# Power.net
KiCad netlist of a schematic drawn in Altium Designer
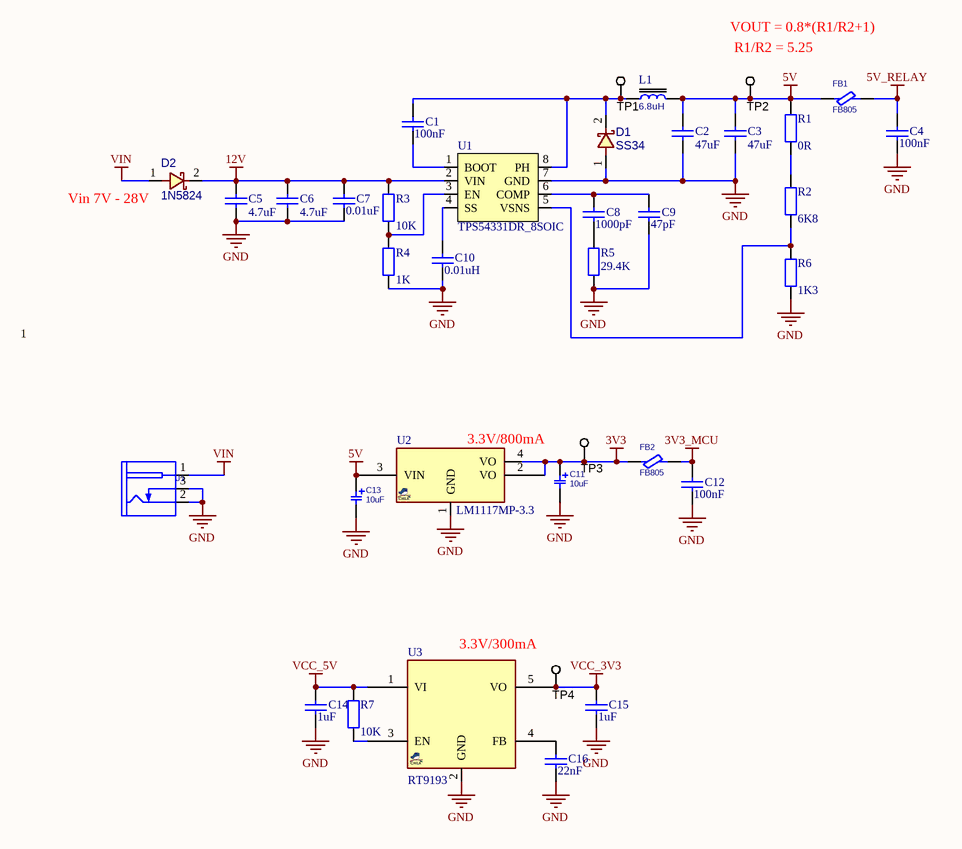
[diagram p0: Power.SchDoc]

(export (version "E")
  (design (tool "Eeschema 10.0.6"))
  (components
    (comp (ref "C1")
      (value "100nF_0603_1%")
      (footprint "tu 0603")
      (description "Capacitor, Ceramic, 50V")
      (fields (field (name "MA_HANG") "100nF"))
      (libsource (lib "THU VIEN SCH") (part "Tu 0603 470pF 50V 10%"))
    )
    (comp (ref "C2")
      (value "47uF_1206_1%")
      (footprint "tu 1206")
      (description "Capacitor, Ceramic, 50V")
      (fields (field (name "MA_HANG") "47uF"))
      (libsource (lib "THU VIEN SCH") (part "Tu 1206 103 50V 10%"))
    )
    (comp (ref "C3")
      (value "47uF_1206_1%")
      (footprint "tu 1206")
      (description "Capacitor, Ceramic, 50V")
      (fields (field (name "MA_HANG") "47uF"))
      (libsource (lib "THU VIEN SCH") (part "Tu 1206 103 50V 10%"))
    )
    (comp (ref "C4")
      (value "100nF_0603_1%")
      (footprint "tu 0603")
      (description "Capacitor, Ceramic, 50V")
      (fields (field (name "MA_HANG") "100nF"))
      (libsource (lib "THU VIEN SCH") (part "Tu 0603 470pF 50V 10%"))
    )
    (comp (ref "C5")
      (value "4.7uF_1206_1%")
      (footprint "tu 1206")
      (description "Capacitor, Ceramic, 50V")
      (fields (field (name "MA_HANG") "4.7uF"))
      (libsource (lib "THU VIEN SCH") (part "Tu 1206 103 50V 10%"))
    )
    (comp (ref "C6")
      (value "4.7uF_1206_1%")
      (footprint "tu 1206")
      (description "Capacitor, Ceramic, 50V")
      (fields (field (name "MA_HANG") "4.7uF"))
      (libsource (lib "THU VIEN SCH") (part "Tu 1206 103 50V 10%"))
    )
    (comp (ref "C7")
      (value "0.01uF_0603_1%")
      (footprint "tu 0603")
      (description "Capacitor, Ceramic, 50V")
      (fields (field (name "MA_HANG") "0.01uF"))
      (libsource (lib "THU VIEN SCH") (part "Tu 0603 470pF 50V 10%"))
    )
    (comp (ref "C8")
      (value "1000pF_0603_1%")
      (footprint "tu 0603")
      (description "Capacitor, Ceramic, 50V")
      (fields (field (name "MA_HANG") "1000pF"))
      (libsource (lib "THU VIEN SCH") (part "Tu 0603 470pF 50V 10%"))
    )
    (comp (ref "C9")
      (value "47pF_0603_1%")
      (footprint "tu 0603")
      (description "Capacitor, Ceramic, 50V")
      (fields (field (name "MA_HANG") "47pF"))
      (libsource (lib "THU VIEN SCH") (part "Tu 0603 470pF 50V 10%"))
    )
    (comp (ref "C10")
      (value "0.01uF_0603_1%")
      (footprint "tu 0603")
      (description "CAP SMD 0603")
      (fields (field (name "MA_HANG") "0.01uH"))
      (libsource (lib "THU VIEN SCH") (part "Tu 0603 470pF 50V 10%"))
    )
    (comp (ref "C11")
      (value "10uF")
      (footprint "C_TN_3216")
      (description "CAP, SMD, TAN")
      (fields (field (name "MANF") "VISHAY") (field (name "MANF_P#") "T55A106M6R3C0300"))
      (libsource (lib "AH_Library") (part "CAP_SMD_TAN_10uF_6.3V"))
    )
    (comp (ref "C12")
      (value "100nF_0603_1%")
      (footprint "tu 0603")
      (description "Capacitor, Ceramic, 50V")
      (fields (field (name "MA_HANG") "100nF"))
      (libsource (lib "THU VIEN SCH") (part "Tu 0603 470pF 50V 10%"))
    )
    (comp (ref "C13")
      (value "10uF")
      (footprint "C_TN_3216")
      (description "CAP, SMD, TAN")
      (fields (field (name "MANF") "VISHAY") (field (name "MANF_P#") "T55A106M010C0300"))
      (libsource (lib "AH_Library") (part "CAP_SMD_TAN_10uF_10V"))
    )
    (comp (ref "C14")
      (value "1uF_0603_1%")
      (footprint "tu 0603")
      (description "Capacitor, Ceramic, 50V")
      (fields (field (name "MA_HANG") "1uF"))
      (libsource (lib "THU VIEN SCH") (part "Tu 0603 470pF 50V 10%"))
    )
    (comp (ref "C15")
      (value "1uF_0603_1%")
      (footprint "tu 0603")
      (description "Capacitor, Ceramic, 50V")
      (fields (field (name "MA_HANG") "1uF"))
      (libsource (lib "THU VIEN SCH") (part "Tu 0603 470pF 50V 10%"))
    )
    (comp (ref "C16")
      (value "22nF_0603_1%")
      (footprint "tu 0603")
      (description "Capacitor, Ceramic, 50V")
      (fields (field (name "MA_HANG") "22nF"))
      (libsource (lib "THU VIEN SCH") (part "Tu 0603 470pF 50V 10%"))
    )
    (comp (ref "D1")
      (value "SS34")
      (footprint "D_SMB")
      (description "DIODE, SCHOTTKY, 20V, 3A")
      (fields (field (name "MANF") "VISHAY") (field (name "Comment") "SS34_SMA"))
      (libsource (lib "AH_Library") (part "DIODE_SMD_SCHOTTKY_SS34"))
    )
    (comp (ref "D2")
      (value "1N5824")
      (footprint "D_SMA")
      (description "DIODE, SCHOTTKY, 40V, 3A")
      (fields (field (name "MANF") "DIODES") (field (name "MANF_P#") "1N5822"))
      (libsource (lib "AH_Library") (part "DIODE_SMD_SCHOTTKY_1N5822"))
    )
    (comp (ref "FB1")
      (value "FB805")
      (footprint "L0805")
      (description "FERRITE_Bead, 0805, 2A, 50mOhm, 220@100MHz")
      (fields (field (name "MANF") "MURATA") (field (name "MANF_P#") "BLM15AG121SN1D"))
      (libsource (lib "AH_Library") (part "FBEAD_SMD_BLM21PG221"))
    )
    (comp (ref "FB2")
      (value "FB805")
      (footprint "L0805")
      (description "FERRITE_Bead, 0805, 2A, 50mOhm, 220@100MHz")
      (fields (field (name "MANF") "MURATA") (field (name "MANF_P#") "BLM15AG121SN1D"))
      (libsource (lib "AH_Library") (part "FBEAD_SMD_BLM21PG221"))
    )
    (comp (ref "J1")
      (value "DC_POWER_JACK")
      (footprint "JAC_PWR2")
      (description "CONN, PWR JACK DC, PLUG DIAM 2.0MM RA THD")
      (fields
        (field (name "MANF") "CUI STACK")
        (field (name "MANF_P#") "PJ-202A, PJ-002AH, PJ-102AH, KLDX-0202")
      )
      (libsource (lib "AH_Library") (part "CONN_PWR_JACKR2"))
    )
    (comp (ref "L1")
      (value "6.8uH")
      (footprint "L_10")
      (description "INDUCTOR, POWER, SMD")
      (fields (field (name "Comment") "6.8uH_CD104"))
      (libsource (lib "AH_Library") (part "INDPWR_SMD"))
    )
    (comp (ref "R1")
      (value "0R_0603_1%")
      (footprint "tro smd 0603")
      (description "RES SMD 0603")
      (fields (field (name "MA_HANG") "0R"))
      (libsource (lib "THU VIEN SCH") (part "Tro 0603 5% 10k"))
    )
    (comp (ref "R2")
      (value "6K8_0603_1%")
      (footprint "tro smd 0603")
      (description "RES SMD 0603")
      (fields (field (name "MA_HANG") "6K8"))
      (libsource (lib "THU VIEN SCH") (part "Tro 0603 5% 10k"))
    )
    (comp (ref "R3")
      (value "10K_0603_1%")
      (footprint "tro smd 0603")
      (description "RES SMD 0603")
      (fields (field (name "MA_HANG") "10K"))
      (libsource (lib "THU VIEN SCH") (part "Tro 0603 5% 10k"))
    )
    (comp (ref "R4")
      (value "1K_0603_1%")
      (footprint "tro smd 0603")
      (description "RES SMD 0603")
      (fields (field (name "MA_HANG") "1K"))
      (libsource (lib "THU VIEN SCH") (part "Tro 0603 5% 10k"))
    )
    (comp (ref "R5")
      (value "29.4K_0805_1%")
      (footprint "tro smd 0805")
      (description "Dán")
      (fields (field (name "MA_HANG") "29.4K"))
      (libsource (lib "THU VIEN SCH") (part "Tro 0805 1% 5.1k"))
    )
    (comp (ref "R6")
      (value "1K3_0603_1%")
      (footprint "tro smd 0603")
      (description "RES SMD 0603")
      (fields (field (name "MA_HANG") "1K3"))
      (libsource (lib "THU VIEN SCH") (part "Tro 0603 5% 10k"))
    )
    (comp (ref "R7")
      (value "10K_0603_1%")
      (footprint "tro smd 0603")
      (description "RES SMD 0603")
      (fields (field (name "MA_HANG") "10K"))
      (libsource (lib "THU VIEN SCH") (part "Tro 0603 5% 10k"))
    )
    (comp (ref "TP1")
      (value "TESTPOINT_PROBE")
      (footprint "TEST_POINT_1.0X1.0MM")
      (description "TEST POINT")
      (fields (field (name "MANF") "MANF") (field (name "MANF_P#") "MANF_P#"))
      (libsource (lib "AH_Library") (part "TESTPOINT_PROBE"))
    )
    (comp (ref "TP2")
      (value "TESTPOINT_PROBE")
      (footprint "TEST_POINT_1.0X1.0MM")
      (description "TEST POINT")
      (fields (field (name "MANF") "MANF") (field (name "MANF_P#") "MANF_P#"))
      (libsource (lib "AH_Library") (part "TESTPOINT_PROBE"))
    )
    (comp (ref "TP3")
      (value "TESTPOINT_PROBE")
      (footprint "TEST_POINT_1.0X1.0MM")
      (description "TEST POINT")
      (fields (field (name "MANF") "MANF") (field (name "MANF_P#") "MANF_P#"))
      (libsource (lib "AH_Library") (part "TESTPOINT_PROBE"))
    )
    (comp (ref "TP4")
      (value "TESTPOINT_PROBE")
      (footprint "TEST_POINT_1.0X1.0MM")
      (description "TEST POINT")
      (fields (field (name "MANF") "MANF") (field (name "MANF_P#") "MANF_P#"))
      (libsource (lib "AH_Library") (part "TESTPOINT_PROBE"))
    )
    (comp (ref "U1")
      (value "TPS54331DR_8SOIC")
      (footprint "SOIC-8N")
      (description "IC REG BUCK ADJ 3A 8SOIC")
      (libsource (lib "PCB_Project_Dangrangto") (part "TPS54331DR"))
    )
    (comp (ref "U2")
      (value "LM1117MP-3.3")
      (footprint "SOT223_4")
      (description "REG, Linear, LDO1V, 0.8A, SOT-223")
      (fields
        (field (name "MANF_P#") "LD1117, LM1117, AMS1117, TLV1117, REG1117, NCP1117, LT1117, SPX1117")
        (field (name "MANF") "TI, ON, ST")
      )
      (libsource (lib "AH_Library") (part "VREG_1117_SOT223"))
    )
    (comp (ref "U3")
      (value "RT9193")
      (footprint "SOT23_5")
      (description "REG, Linear, LDO, SOT-23-5")
      (libsource (lib "AH_Library") (part "VREG_LDO_SOT23_5"))
    )
  )
  (nets
    (net (code "1") (name "3V3") (class "Default")
      (node (ref "C11") (pin "1") (pinfunction "1_1") (pintype "passive"))
      (node (ref "FB2") (pin "1") (pinfunction "1_1") (pintype "passive"))
      (node (ref "TP3") (pin "1") (pinfunction "1_1") (pintype "passive"))
      (node (ref "U2") (pin "2") (pinfunction "VO_2") (pintype "passive"))
      (node (ref "U2") (pin "4") (pinfunction "VO_4") (pintype "passive"))
    )
    (net (code "2") (name "3V3_MCU") (class "Default")
      (node (ref "C12") (pin "1") (pinfunction "1_1") (pintype "passive"))
      (node (ref "FB2") (pin "2") (pinfunction "2_2") (pintype "passive"))
    )
    (net (code "3") (name "5V") (class "Default")
      (node (ref "C13") (pin "1") (pinfunction "1_1") (pintype "passive"))
      (node (ref "C2") (pin "1") (pinfunction "1_1") (pintype "passive"))
      (node (ref "C3") (pin "1") (pinfunction "1_1") (pintype "passive"))
      (node (ref "FB1") (pin "1") (pinfunction "1_1") (pintype "passive"))
      (node (ref "L1") (pin "2") (pinfunction "2_2") (pintype "passive"))
      (node (ref "R1") (pin "2") (pinfunction "2_2") (pintype "passive"))
      (node (ref "TP2") (pin "1") (pinfunction "1_1") (pintype "passive"))
      (node (ref "U2") (pin "3") (pinfunction "VIN_3") (pintype "passive"))
    )
    (net (code "4") (name "5V_RELAY") (class "Default")
      (node (ref "C4") (pin "1") (pinfunction "1_1") (pintype "passive"))
      (node (ref "FB1") (pin "2") (pinfunction "2_2") (pintype "passive"))
    )
    (net (code "5") (name "12V") (class "Default")
      (node (ref "C5") (pin "1") (pinfunction "1_1") (pintype "passive"))
      (node (ref "C6") (pin "1") (pinfunction "1_1") (pintype "passive"))
      (node (ref "C7") (pin "1") (pinfunction "1_1") (pintype "passive"))
      (node (ref "D2") (pin "2") (pinfunction "2_2") (pintype "passive"))
      (node (ref "R3") (pin "2") (pinfunction "2_2") (pintype "passive"))
      (node (ref "U1") (pin "2") (pinfunction "VIN_2") (pintype "passive"))
    )
    (net (code "6") (name "GND") (class "Default")
      (node (ref "C10") (pin "2") (pinfunction "2_2") (pintype "passive"))
      (node (ref "C11") (pin "2") (pinfunction "2_2") (pintype "passive"))
      (node (ref "C12") (pin "2") (pinfunction "2_2") (pintype "passive"))
      (node (ref "C13") (pin "2") (pinfunction "2_2") (pintype "passive"))
      (node (ref "C14") (pin "2") (pinfunction "2_2") (pintype "passive"))
      (node (ref "C15") (pin "2") (pinfunction "2_2") (pintype "passive"))
      (node (ref "C16") (pin "2") (pinfunction "2_2") (pintype "passive"))
      (node (ref "C2") (pin "2") (pinfunction "2_2") (pintype "passive"))
      (node (ref "C3") (pin "2") (pinfunction "2_2") (pintype "passive"))
      (node (ref "C4") (pin "2") (pinfunction "2_2") (pintype "passive"))
      (node (ref "C5") (pin "2") (pinfunction "2_2") (pintype "passive"))
      (node (ref "C6") (pin "2") (pinfunction "2_2") (pintype "passive"))
      (node (ref "C7") (pin "2") (pinfunction "2_2") (pintype "passive"))
      (node (ref "C9") (pin "2") (pinfunction "2_2") (pintype "passive"))
      (node (ref "D1") (pin "1") (pinfunction "1_1") (pintype "passive"))
      (node (ref "J1") (pin "2") (pinfunction "SLEEVE_2") (pintype "power_in"))
      (node (ref "J1") (pin "3") (pinfunction "INSERTION_DET_3") (pintype "power_in"))
      (node (ref "R4") (pin "1") (pinfunction "1_1") (pintype "passive"))
      (node (ref "R5") (pin "1") (pinfunction "1_1") (pintype "passive"))
      (node (ref "R6") (pin "1") (pinfunction "1_1") (pintype "passive"))
      (node (ref "U1") (pin "7") (pinfunction "GND_7") (pintype "passive"))
      (node (ref "U2") (pin "1") (pinfunction "GND_1") (pintype "passive"))
      (node (ref "U3") (pin "2") (pinfunction "GND_2") (pintype "passive"))
    )
    (net (code "7") (name "Net-(C8-Pad2)") (class "Default")
      (node (ref "C8") (pin "2") (pinfunction "2_2") (pintype "passive"))
      (node (ref "R5") (pin "2") (pinfunction "2_2") (pintype "passive"))
    )
    (net (code "8") (name "Net-(R1-Pad1)") (class "Default")
      (node (ref "R1") (pin "1") (pinfunction "1_1") (pintype "passive"))
      (node (ref "R2") (pin "2") (pinfunction "2_2") (pintype "passive"))
    )
    (net (code "9") (name "Net-(U1-BOOT)") (class "Default")
      (node (ref "C1") (pin "2") (pinfunction "2_2") (pintype "passive"))
      (node (ref "U1") (pin "1") (pinfunction "BOOT_1") (pintype "passive"))
    )
    (net (code "10") (name "Net-(U1-COMP)") (class "Default")
      (node (ref "C8") (pin "1") (pinfunction "1_1") (pintype "passive"))
      (node (ref "C9") (pin "1") (pinfunction "1_1") (pintype "passive"))
      (node (ref "U1") (pin "6") (pinfunction "COMP_6") (pintype "passive"))
    )
    (net (code "11") (name "Net-(U1-EN)") (class "Default")
      (node (ref "R3") (pin "1") (pinfunction "1_1") (pintype "passive"))
      (node (ref "R4") (pin "2") (pinfunction "2_2") (pintype "passive"))
      (node (ref "U1") (pin "3") (pinfunction "EN_3") (pintype "passive"))
    )
    (net (code "12") (name "Net-(U1-PH)") (class "Default")
      (node (ref "C1") (pin "1") (pinfunction "1_1") (pintype "passive"))
      (node (ref "D1") (pin "2") (pinfunction "2_2") (pintype "passive"))
      (node (ref "L1") (pin "1") (pinfunction "1_1") (pintype "passive"))
      (node (ref "TP1") (pin "1") (pinfunction "1_1") (pintype "passive"))
      (node (ref "U1") (pin "8") (pinfunction "PH_8") (pintype "passive"))
    )
    (net (code "13") (name "Net-(U1-SS)") (class "Default")
      (node (ref "C10") (pin "1") (pinfunction "1_1") (pintype "passive"))
      (node (ref "U1") (pin "4") (pinfunction "SS_4") (pintype "passive"))
    )
    (net (code "14") (name "Net-(U1-VSNS)") (class "Default")
      (node (ref "R2") (pin "1") (pinfunction "1_1") (pintype "passive"))
      (node (ref "R6") (pin "2") (pinfunction "2_2") (pintype "passive"))
      (node (ref "U1") (pin "5") (pinfunction "VSNS_5") (pintype "passive"))
    )
    (net (code "15") (name "Net-(U3-EN)") (class "Default")
      (node (ref "R7") (pin "1") (pinfunction "1_1") (pintype "passive"))
      (node (ref "U3") (pin "3") (pinfunction "EN_3") (pintype "passive"))
    )
    (net (code "16") (name "Net-(U3-FB)") (class "Default")
      (node (ref "C16") (pin "1") (pinfunction "1_1") (pintype "passive"))
      (node (ref "U3") (pin "4") (pinfunction "FB_4") (pintype "passive"))
    )
    (net (code "17") (name "VCC_3V3") (class "Default")
      (node (ref "C15") (pin "1") (pinfunction "1_1") (pintype "passive"))
      (node (ref "TP4") (pin "1") (pinfunction "1_1") (pintype "passive"))
      (node (ref "U3") (pin "5") (pinfunction "VO_5") (pintype "passive"))
    )
    (net (code "18") (name "VCC_5V") (class "Default")
      (node (ref "C14") (pin "1") (pinfunction "1_1") (pintype "passive"))
      (node (ref "R7") (pin "2") (pinfunction "2_2") (pintype "passive"))
      (node (ref "U3") (pin "1") (pinfunction "VI_1") (pintype "passive"))
    )
    (net (code "19") (name "VIN") (class "Default")
      (node (ref "D2") (pin "1") (pinfunction "1_1") (pintype "passive"))
      (node (ref "J1") (pin "1") (pinfunction "TIP_1") (pintype "power_in"))
    )
  )
)
